# High_Voltage.net
KiCad netlist of a schematic drawn in Altium Designer
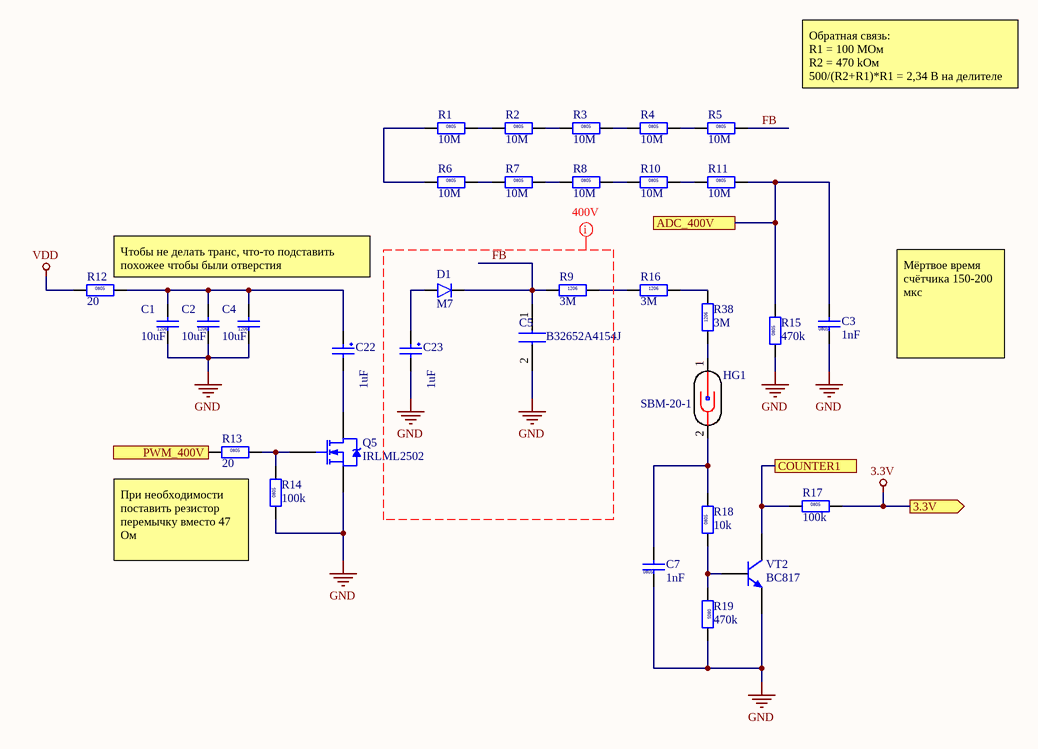
[diagram p0: High_Voltage.SchDoc]

(export (version "E")
  (design (tool "Eeschema 10.0.6"))
  (components
    (comp (ref "C1")
      (value "10uF")
      (footprint "CAPC3216-1206L")
      (description "Capacitor 1206")
      (fields (field (name "Comment") "CAPC_1206"))
      (libsource (lib "Passive") (part "CAPC_1206"))
    )
    (comp (ref "C2")
      (value "10uF")
      (footprint "CAPC3216-1206L")
      (description "Capacitor 1206")
      (fields (field (name "Comment") "CAPC_1206"))
      (libsource (lib "Passive") (part "CAPC_1206"))
    )
    (comp (ref "C3")
      (value "1nF")
      (footprint "CAPC2012-0805M")
      (description "Capacitor 0805")
      (fields (field (name "Comment") "CAPC_0805"))
      (libsource (lib "Passive") (part "CAPC_0805"))
    )
    (comp (ref "C4")
      (value "10uF")
      (footprint "CAPC3216-1206L")
      (description "Capacitor 1206")
      (fields (field (name "Comment") "CAPC_1206"))
      (libsource (lib "Passive") (part "CAPC_1206"))
    )
    (comp (ref "C5")
      (value "B32652A4154J")
      (footprint "SamacSys:B32652A4154J")
      (description "Capacitor")
      (fields (field (name "MOUSER PART NUMBER") "871-B32652A4154J"))
      (libsource (lib "*") (part "B32652A4154J"))
    )
    (comp (ref "C7")
      (value "1nF")
      (footprint "CAPC2012-0805M")
      (description "Capacitor 0805")
      (fields (field (name "Comment") "CAPC_0805"))
      (libsource (lib "Passive") (part "CAPC_0805"))
    )
    (comp (ref "C22")
      (value "1uF")
      (footprint "ECAP811.5")
      (description "Capacitor electrolytic 3.5 mm pitch, 8*11.5 body")
      (fields (field (name "Comment") "ECAP-811.5"))
      (libsource (lib "Passive") (part "ECAP-811.5"))
    )
    (comp (ref "C23")
      (value "1uF")
      (footprint "ECAP16315")
      (description "Capacitor electrolytic 7.5 mm pitch, 16*25 body")
      (fields (field (name "Comment") "ECAP-1625"))
      (libsource (lib "Passive") (part "ECAP-1625"))
    )
    (comp (ref "D1")
      (value "M7")
      (footprint "DIOM5026X262N")
      (description "Diode")
      (fields (field (name "MANUFACTURER_PART_NUMBER") "SS34A"))
      (libsource (lib "M7 diode") (part "M7"))
    )
    (comp (ref "HG1")
      (value "SBM-20-1")
      (footprint "SBM-20-1")
      (libsource (lib "Bogdanov") (part "SBM-20-1"))
    )
    (comp (ref "Q5")
      (value "IRLML2502")
      (footprint "SOT23-3L")
      (description "IRLML2502 Hexfet power MOSFET")
      (libsource (lib "Discrete") (part "IRLML2502"))
    )
    (comp (ref "R1")
      (value "10M")
      (footprint "RESC2012-0805M")
      (description "Resistor 0805")
      (fields (field (name "Comment") "RESC_0805_R"))
      (libsource (lib "Passive") (part "RESC_0805_R"))
    )
    (comp (ref "R2")
      (value "10M")
      (footprint "RESC2012-0805M")
      (description "Resistor 0805")
      (fields (field (name "Comment") "RESC_0805_R"))
      (libsource (lib "Passive") (part "RESC_0805_R"))
    )
    (comp (ref "R3")
      (value "10M")
      (footprint "RESC2012-0805M")
      (description "Resistor 0805")
      (fields (field (name "Comment") "RESC_0805_R"))
      (libsource (lib "Passive") (part "RESC_0805_R"))
    )
    (comp (ref "R4")
      (value "10M")
      (footprint "RESC2012-0805M")
      (description "Resistor 0805")
      (fields (field (name "Comment") "RESC_0805_R"))
      (libsource (lib "Passive") (part "RESC_0805_R"))
    )
    (comp (ref "R5")
      (value "10M")
      (footprint "RESC2012-0805M")
      (description "Resistor 0805")
      (fields (field (name "Comment") "RESC_0805_R"))
      (libsource (lib "Passive") (part "RESC_0805_R"))
    )
    (comp (ref "R6")
      (value "10M")
      (footprint "RESC2012-0805M")
      (description "Resistor 0805")
      (fields (field (name "Comment") "RESC_0805_R"))
      (libsource (lib "Passive") (part "RESC_0805_R"))
    )
    (comp (ref "R7")
      (value "10M")
      (footprint "RESC2012-0805M")
      (description "Resistor 0805")
      (fields (field (name "Comment") "RESC_0805_R"))
      (libsource (lib "Passive") (part "RESC_0805_R"))
    )
    (comp (ref "R8")
      (value "10M")
      (footprint "RESC2012-0805M")
      (description "Resistor 0805")
      (fields (field (name "Comment") "RESC_0805_R"))
      (libsource (lib "Passive") (part "RESC_0805_R"))
    )
    (comp (ref "R9")
      (value "3M")
      (footprint "RESC3216-1206M")
      (description "Resistor 1206")
      (fields (field (name "Comment") "RESC_1206_R"))
      (libsource (lib "") (part "RESC_1206_R_1"))
    )
    (comp (ref "R10")
      (value "10M")
      (footprint "RESC2012-0805M")
      (description "Resistor 0805")
      (fields (field (name "Comment") "RESC_0805_R"))
      (libsource (lib "Passive") (part "RESC_0805_R"))
    )
    (comp (ref "R11")
      (value "10M")
      (footprint "RESC2012-0805M")
      (description "Resistor 0805")
      (fields (field (name "Comment") "RESC_0805_R"))
      (libsource (lib "Passive") (part "RESC_0805_R"))
    )
    (comp (ref "R12")
      (value "20")
      (footprint "RESC2012-0805M")
      (description "Resistor 0805")
      (fields (field (name "Comment") "RESC_0805_R"))
      (libsource (lib "Passive") (part "RESC_0805_R"))
    )
    (comp (ref "R13")
      (value "20")
      (footprint "RESC2012-0805M")
      (description "Resistor 0805")
      (fields (field (name "Comment") "RESC_0805_R"))
      (libsource (lib "Passive") (part "RESC_0805_R"))
    )
    (comp (ref "R14")
      (value "100k")
      (footprint "RESC2012-0805M")
      (description "Resistor 0805")
      (fields (field (name "Comment") "RESC_0805_R"))
      (libsource (lib "") (part "RESC_0805_R_1"))
    )
    (comp (ref "R15")
      (value "470k")
      (footprint "RESC2012-0805M")
      (description "Resistor 0805")
      (fields (field (name "Comment") "RESC_0805_R"))
      (libsource (lib "") (part "RESC_0805_R_1"))
    )
    (comp (ref "R16")
      (value "3M")
      (footprint "RESC3216-1206M")
      (description "Resistor 1206")
      (fields (field (name "Comment") "RESC_1206_R"))
      (libsource (lib "") (part "RESC_1206_R_1"))
    )
    (comp (ref "R17")
      (value "100k")
      (footprint "RESC2012-0805M")
      (description "Resistor 0805")
      (fields (field (name "Comment") "RESC_0805_R"))
      (libsource (lib "Passive") (part "RESC_0805_R"))
    )
    (comp (ref "R18")
      (value "10k")
      (footprint "RESC2012-0805M")
      (description "Resistor 0805")
      (fields (field (name "Comment") "RESC_0805_R"))
      (libsource (lib "") (part "RESC_0805_R_1"))
    )
    (comp (ref "R19")
      (value "470k")
      (footprint "RESC2012-0805M")
      (description "Resistor 0805")
      (fields (field (name "Comment") "RESC_0805_R"))
      (libsource (lib "") (part "RESC_0805_R_2"))
    )
    (comp (ref "R38")
      (value "3M")
      (footprint "RESC3216-1206M")
      (description "Resistor 1206")
      (fields (field (name "Comment") "RESC_1206_R"))
      (libsource (lib "Passive") (part "RESC_1206_R"))
    )
    (comp (ref "VT2")
      (value "BC817")
      (footprint "SOT23-3M")
      (description "BC817 NPN Transistor")
      (libsource (lib "Discrete") (part "BC817"))
    )
  )
  (nets
    (net (code "1") (name "/ADC_400V") (class "Default")
      (node (ref "C3") (pin "2") (pinfunction "2_2") (pintype "passive"))
      (node (ref "R11") (pin "2") (pinfunction "2_2") (pintype "passive"))
      (node (ref "R15") (pin "2") (pinfunction "2_2") (pintype "passive"))
    )
    (net (code "2") (name "/COUNTER1") (class "Default")
      (node (ref "R17") (pin "1") (pinfunction "1_1") (pintype "passive"))
      (node (ref "VT2") (pin "3") (pinfunction "C_3") (pintype "passive"))
    )
    (net (code "3") (name "/FB") (class "Default")
      (node (ref "C5") (pin "1") (pinfunction "1_1") (pintype "passive"))
      (node (ref "D1") (pin "1") (pinfunction "K_1") (pintype "passive"))
      (node (ref "R5") (pin "2") (pinfunction "2_2") (pintype "passive"))
      (node (ref "R9") (pin "1") (pinfunction "1_1") (pintype "passive"))
    )
    (net (code "4") (name "/PWM_400V") (class "Default")
      (node (ref "R13") (pin "1") (pinfunction "1_1") (pintype "passive"))
    )
    (net (code "5") (name "3.3V") (class "Default")
      (node (ref "R17") (pin "2") (pinfunction "2_2") (pintype "passive"))
    )
    (net (code "6") (name "GND") (class "Default")
      (node (ref "C1") (pin "1") (pinfunction "1_1") (pintype "passive"))
      (node (ref "C2") (pin "1") (pinfunction "1_1") (pintype "passive"))
      (node (ref "C23") (pin "2") (pinfunction "2_2") (pintype "passive"))
      (node (ref "C3") (pin "1") (pinfunction "1_1") (pintype "passive"))
      (node (ref "C4") (pin "1") (pinfunction "1_1") (pintype "passive"))
      (node (ref "C5") (pin "2") (pinfunction "2_2") (pintype "passive"))
      (node (ref "C7") (pin "1") (pinfunction "1_1") (pintype "passive"))
      (node (ref "Q5") (pin "2") (pinfunction "S_2") (pintype "passive"))
      (node (ref "R14") (pin "1") (pinfunction "1_1") (pintype "passive"))
      (node (ref "R15") (pin "1") (pinfunction "1_1") (pintype "passive"))
      (node (ref "R19") (pin "2") (pinfunction "2_2") (pintype "passive"))
      (node (ref "VT2") (pin "2") (pinfunction "E_2") (pintype "passive"))
    )
    (net (code "7") (name "Net-(C1-Pad2)") (class "Default")
      (node (ref "C1") (pin "2") (pinfunction "2_2") (pintype "passive"))
      (node (ref "C2") (pin "2") (pinfunction "2_2") (pintype "passive"))
      (node (ref "C22") (pin "1") (pinfunction "1_1") (pintype "passive"))
      (node (ref "C4") (pin "2") (pinfunction "2_2") (pintype "passive"))
      (node (ref "R12") (pin "2") (pinfunction "2_2") (pintype "passive"))
    )
    (net (code "8") (name "Net-(D1-A)") (class "Default")
      (node (ref "C23") (pin "1") (pinfunction "1_1") (pintype "passive"))
      (node (ref "D1") (pin "2") (pinfunction "A_2") (pintype "passive"))
    )
    (net (code "9") (name "Net-(HG1-A)") (class "Default")
      (node (ref "HG1") (pin "1") (pinfunction "A_1") (pintype "passive"))
      (node (ref "R38") (pin "1") (pinfunction "1_1") (pintype "passive"))
    )
    (net (code "10") (name "Net-(HG1-K)") (class "Default")
      (node (ref "C7") (pin "2") (pinfunction "2_2") (pintype "passive"))
      (node (ref "HG1") (pin "2") (pinfunction "K_2") (pintype "passive"))
      (node (ref "R18") (pin "2") (pinfunction "2_2") (pintype "passive"))
    )
    (net (code "11") (name "Net-(Q5-D)") (class "Default")
      (node (ref "C22") (pin "2") (pinfunction "2_2") (pintype "passive"))
      (node (ref "Q5") (pin "3") (pinfunction "D_3") (pintype "passive"))
    )
    (net (code "12") (name "Net-(Q5-G)") (class "Default")
      (node (ref "Q5") (pin "1") (pinfunction "G_1") (pintype "passive"))
      (node (ref "R13") (pin "2") (pinfunction "2_2") (pintype "passive"))
      (node (ref "R14") (pin "2") (pinfunction "2_2") (pintype "passive"))
    )
    (net (code "13") (name "Net-(R1-Pad1)") (class "Default")
      (node (ref "R1") (pin "1") (pinfunction "1_1") (pintype "passive"))
      (node (ref "R6") (pin "1") (pinfunction "1_1") (pintype "passive"))
    )
    (net (code "14") (name "Net-(R1-Pad2)") (class "Default")
      (node (ref "R1") (pin "2") (pinfunction "2_2") (pintype "passive"))
      (node (ref "R2") (pin "1") (pinfunction "1_1") (pintype "passive"))
    )
    (net (code "15") (name "Net-(R2-Pad2)") (class "Default")
      (node (ref "R2") (pin "2") (pinfunction "2_2") (pintype "passive"))
      (node (ref "R3") (pin "1") (pinfunction "1_1") (pintype "passive"))
    )
    (net (code "16") (name "Net-(R3-Pad2)") (class "Default")
      (node (ref "R3") (pin "2") (pinfunction "2_2") (pintype "passive"))
      (node (ref "R4") (pin "1") (pinfunction "1_1") (pintype "passive"))
    )
    (net (code "17") (name "Net-(R4-Pad2)") (class "Default")
      (node (ref "R4") (pin "2") (pinfunction "2_2") (pintype "passive"))
      (node (ref "R5") (pin "1") (pinfunction "1_1") (pintype "passive"))
    )
    (net (code "18") (name "Net-(R6-Pad2)") (class "Default")
      (node (ref "R6") (pin "2") (pinfunction "2_2") (pintype "passive"))
      (node (ref "R7") (pin "1") (pinfunction "1_1") (pintype "passive"))
    )
    (net (code "19") (name "Net-(R7-Pad2)") (class "Default")
      (node (ref "R7") (pin "2") (pinfunction "2_2") (pintype "passive"))
      (node (ref "R8") (pin "1") (pinfunction "1_1") (pintype "passive"))
    )
    (net (code "20") (name "Net-(R10-Pad1)") (class "Default")
      (node (ref "R10") (pin "1") (pinfunction "1_1") (pintype "passive"))
      (node (ref "R8") (pin "2") (pinfunction "2_2") (pintype "passive"))
    )
    (net (code "21") (name "Net-(R10-Pad2)") (class "Default")
      (node (ref "R10") (pin "2") (pinfunction "2_2") (pintype "passive"))
      (node (ref "R11") (pin "1") (pinfunction "1_1") (pintype "passive"))
    )
    (net (code "22") (name "Net-(R16-Pad1)") (class "Default")
      (node (ref "R16") (pin "1") (pinfunction "1_1") (pintype "passive"))
      (node (ref "R9") (pin "2") (pinfunction "2_2") (pintype "passive"))
    )
    (net (code "23") (name "Net-(R16-Pad2)") (class "Default")
      (node (ref "R16") (pin "2") (pinfunction "2_2") (pintype "passive"))
      (node (ref "R38") (pin "2") (pinfunction "2_2") (pintype "passive"))
    )
    (net (code "24") (name "Net-(VT2-B)") (class "Default")
      (node (ref "R18") (pin "1") (pinfunction "1_1") (pintype "passive"))
      (node (ref "R19") (pin "1") (pinfunction "1_1") (pintype "passive"))
      (node (ref "VT2") (pin "1") (pinfunction "B_1") (pintype "passive"))
    )
    (net (code "25") (name "VDD") (class "Default")
      (node (ref "R12") (pin "1") (pinfunction "1_1") (pintype "passive"))
    )
  )
)
